# m1k-buffermod-d1.net
KiCad netlist of a schematic drawn in EAGLE
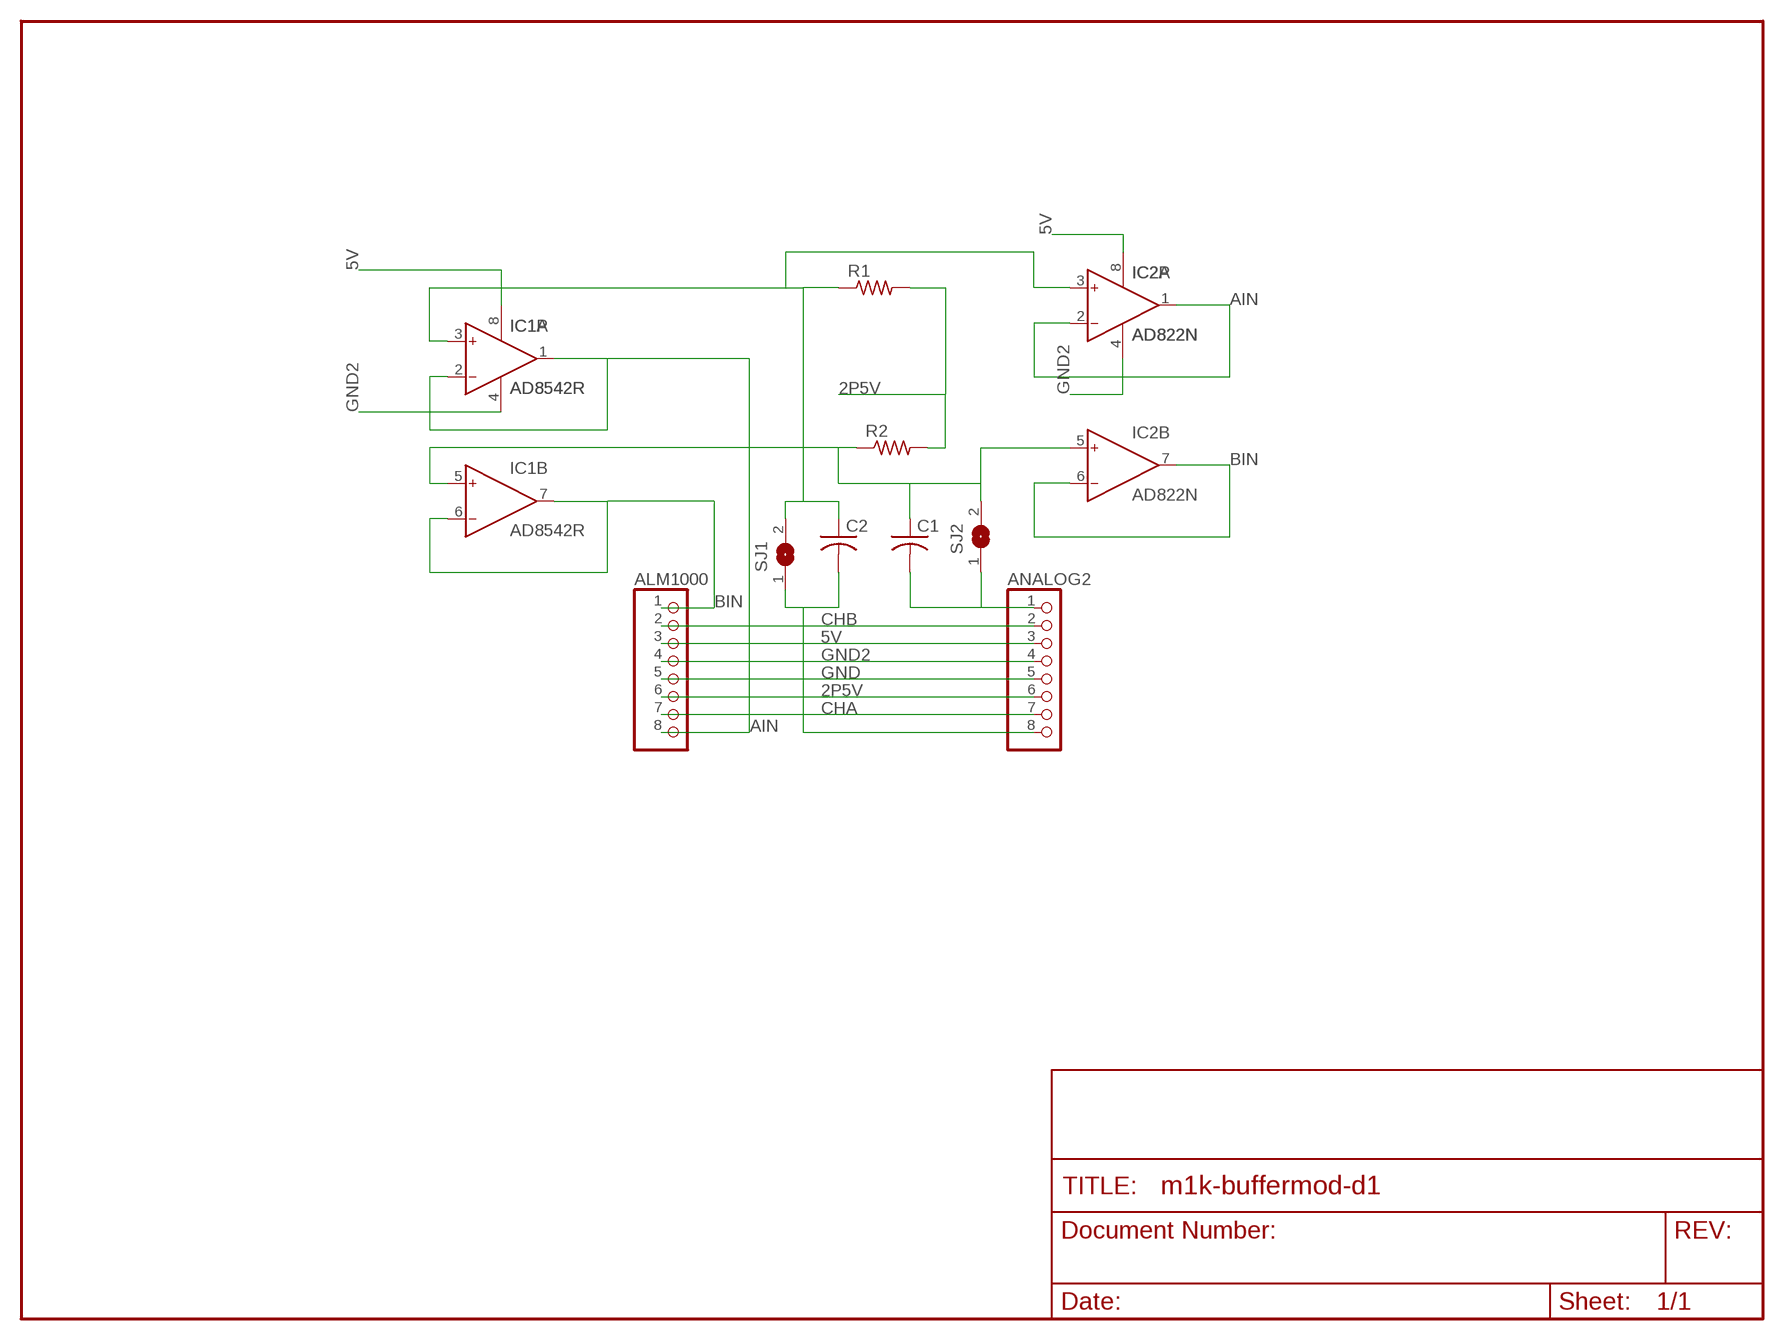
[diagram p0: schematic, sheet 1]

(export (version "E")
  (design (tool "Eeschema 10.0.6"))
  (components
    (comp (ref "ALM1000")
      (value "PINHD-1X8")
      (footprint "eagle-import:1X08")
      (libsource (lib "eagle-import") (part "PINHD-1X8"))
    )
    (comp (ref "ANALOG2")
      (value "PINHD-1X8")
      (footprint "eagle-import:1X08")
      (libsource (lib "eagle-import") (part "PINHD-1X8"))
    )
    (comp (ref "C1")
      (value "C-US050-024X044")
      (footprint "eagle-import:C050-024X044")
      (libsource (lib "eagle-import") (part "C-US050-024X044"))
    )
    (comp (ref "C2")
      (value "C-US050-024X044")
      (footprint "eagle-import:C050-024X044")
      (libsource (lib "eagle-import") (part "C-US050-024X044"))
    )
    (comp (ref "IC1")
      (value "AD8542R")
      (footprint "eagle-import:SO8")
      (fields (field (name "MF") "ALTERA CORPORATION") (field (name "MPN") "AD8542ARZ-REEL"))
      (libsource (lib "eagle-import") (part "AD8542R"))
    )
    (comp (ref "IC2")
      (value "AD822N")
      (footprint "eagle-import:DIL08")
      (libsource (lib "eagle-import") (part "AD822N"))
    )
    (comp (ref "R1")
      (value "R-US_0204/7")
      (footprint "eagle-import:0204_7")
      (libsource (lib "eagle-import") (part "R-US_0204/7"))
    )
    (comp (ref "R2")
      (value "R-US_0204/7")
      (footprint "eagle-import:0204_7")
      (libsource (lib "eagle-import") (part "R-US_0204/7"))
    )
    (comp (ref "SJ1") (value "SJ") (footprint "eagle-import:SJ") (libsource (lib "eagle-import") (part "SJ")))
    (comp (ref "SJ2") (value "SJ") (footprint "eagle-import:SJ") (libsource (lib "eagle-import") (part "SJ")))
  )
  (nets
    (net (code "1") (name "/2P5V") (class "Default")
      (node (ref "ALM1000") (pin "6") (pinfunction "6_6") (pintype "passive"))
      (node (ref "ANALOG2") (pin "6") (pinfunction "6_6") (pintype "passive"))
      (node (ref "R1") (pin "2") (pinfunction "2_2") (pintype "passive"))
      (node (ref "R2") (pin "2") (pinfunction "2_2") (pintype "passive"))
    )
    (net (code "2") (name "/5V") (class "Default")
      (node (ref "ALM1000") (pin "3") (pinfunction "3_3") (pintype "passive"))
      (node (ref "ANALOG2") (pin "3") (pinfunction "3_3") (pintype "passive"))
      (node (ref "IC1") (pin "8") (pinfunction "V+_8") (pintype "power_in"))
      (node (ref "IC2") (pin "8") (pinfunction "V+_8") (pintype "power_in"))
    )
    (net (code "3") (name "/AIN") (class "Default")
      (node (ref "ALM1000") (pin "8") (pinfunction "8_8") (pintype "passive"))
      (node (ref "IC1") (pin "1") (pinfunction "OUT_1") (pintype "output"))
      (node (ref "IC1") (pin "2") (pinfunction "IN-_2") (pintype "input"))
      (node (ref "IC2") (pin "1") (pinfunction "OUT_1") (pintype "output"))
      (node (ref "IC2") (pin "2") (pinfunction "IN-_2") (pintype "input"))
    )
    (net (code "4") (name "/BIN") (class "Default")
      (node (ref "ALM1000") (pin "1") (pinfunction "1_1") (pintype "passive"))
      (node (ref "IC1") (pin "6") (pinfunction "IN-_6") (pintype "input"))
      (node (ref "IC1") (pin "7") (pinfunction "OUT_7") (pintype "output"))
      (node (ref "IC2") (pin "6") (pinfunction "IN-_6") (pintype "input"))
      (node (ref "IC2") (pin "7") (pinfunction "OUT_7") (pintype "output"))
    )
    (net (code "5") (name "/CHA") (class "Default")
      (node (ref "ALM1000") (pin "7") (pinfunction "7_7") (pintype "passive"))
      (node (ref "ANALOG2") (pin "7") (pinfunction "7_7") (pintype "passive"))
    )
    (net (code "6") (name "/CHB") (class "Default")
      (node (ref "ALM1000") (pin "2") (pinfunction "2_2") (pintype "passive"))
      (node (ref "ANALOG2") (pin "2") (pinfunction "2_2") (pintype "passive"))
    )
    (net (code "7") (name "/GND") (class "Default")
      (node (ref "ALM1000") (pin "5") (pinfunction "5_5") (pintype "passive"))
      (node (ref "ANALOG2") (pin "5") (pinfunction "5_5") (pintype "passive"))
    )
    (net (code "8") (name "/GND2") (class "Default")
      (node (ref "ALM1000") (pin "4") (pinfunction "4_4") (pintype "passive"))
      (node (ref "ANALOG2") (pin "4") (pinfunction "4_4") (pintype "passive"))
      (node (ref "IC1") (pin "4") (pinfunction "V-_4") (pintype "power_in"))
      (node (ref "IC2") (pin "4") (pinfunction "V-_4") (pintype "power_in"))
    )
    (net (code "9") (name "Net-(ANALOG2-Pad1)") (class "Default")
      (node (ref "ANALOG2") (pin "1") (pinfunction "1_1") (pintype "passive"))
      (node (ref "C1") (pin "2") (pinfunction "2_2") (pintype "passive"))
      (node (ref "SJ2") (pin "1") (pinfunction "1_1") (pintype "passive"))
    )
    (net (code "10") (name "Net-(ANALOG2-Pad8)") (class "Default")
      (node (ref "ANALOG2") (pin "8") (pinfunction "8_8") (pintype "passive"))
      (node (ref "C2") (pin "2") (pinfunction "2_2") (pintype "passive"))
      (node (ref "SJ1") (pin "1") (pinfunction "1_1") (pintype "passive"))
    )
    (net (code "11") (name "Net-(IC1A-IN+)") (class "Default")
      (node (ref "C2") (pin "1") (pinfunction "1_1") (pintype "passive"))
      (node (ref "IC1") (pin "3") (pinfunction "IN+_3") (pintype "input"))
      (node (ref "IC2") (pin "3") (pinfunction "IN+_3") (pintype "input"))
      (node (ref "R1") (pin "1") (pinfunction "1_1") (pintype "passive"))
      (node (ref "SJ1") (pin "2") (pinfunction "2_2") (pintype "passive"))
    )
    (net (code "12") (name "Net-(IC1B-IN+)") (class "Default")
      (node (ref "C1") (pin "1") (pinfunction "1_1") (pintype "passive"))
      (node (ref "IC1") (pin "5") (pinfunction "IN+_5") (pintype "input"))
      (node (ref "IC2") (pin "5") (pinfunction "IN+_5") (pintype "input"))
      (node (ref "R2") (pin "1") (pinfunction "1_1") (pintype "passive"))
      (node (ref "SJ2") (pin "2") (pinfunction "2_2") (pintype "passive"))
    )
  )
)
